# io_board.net
KiCad netlist of a schematic drawn in EAGLE
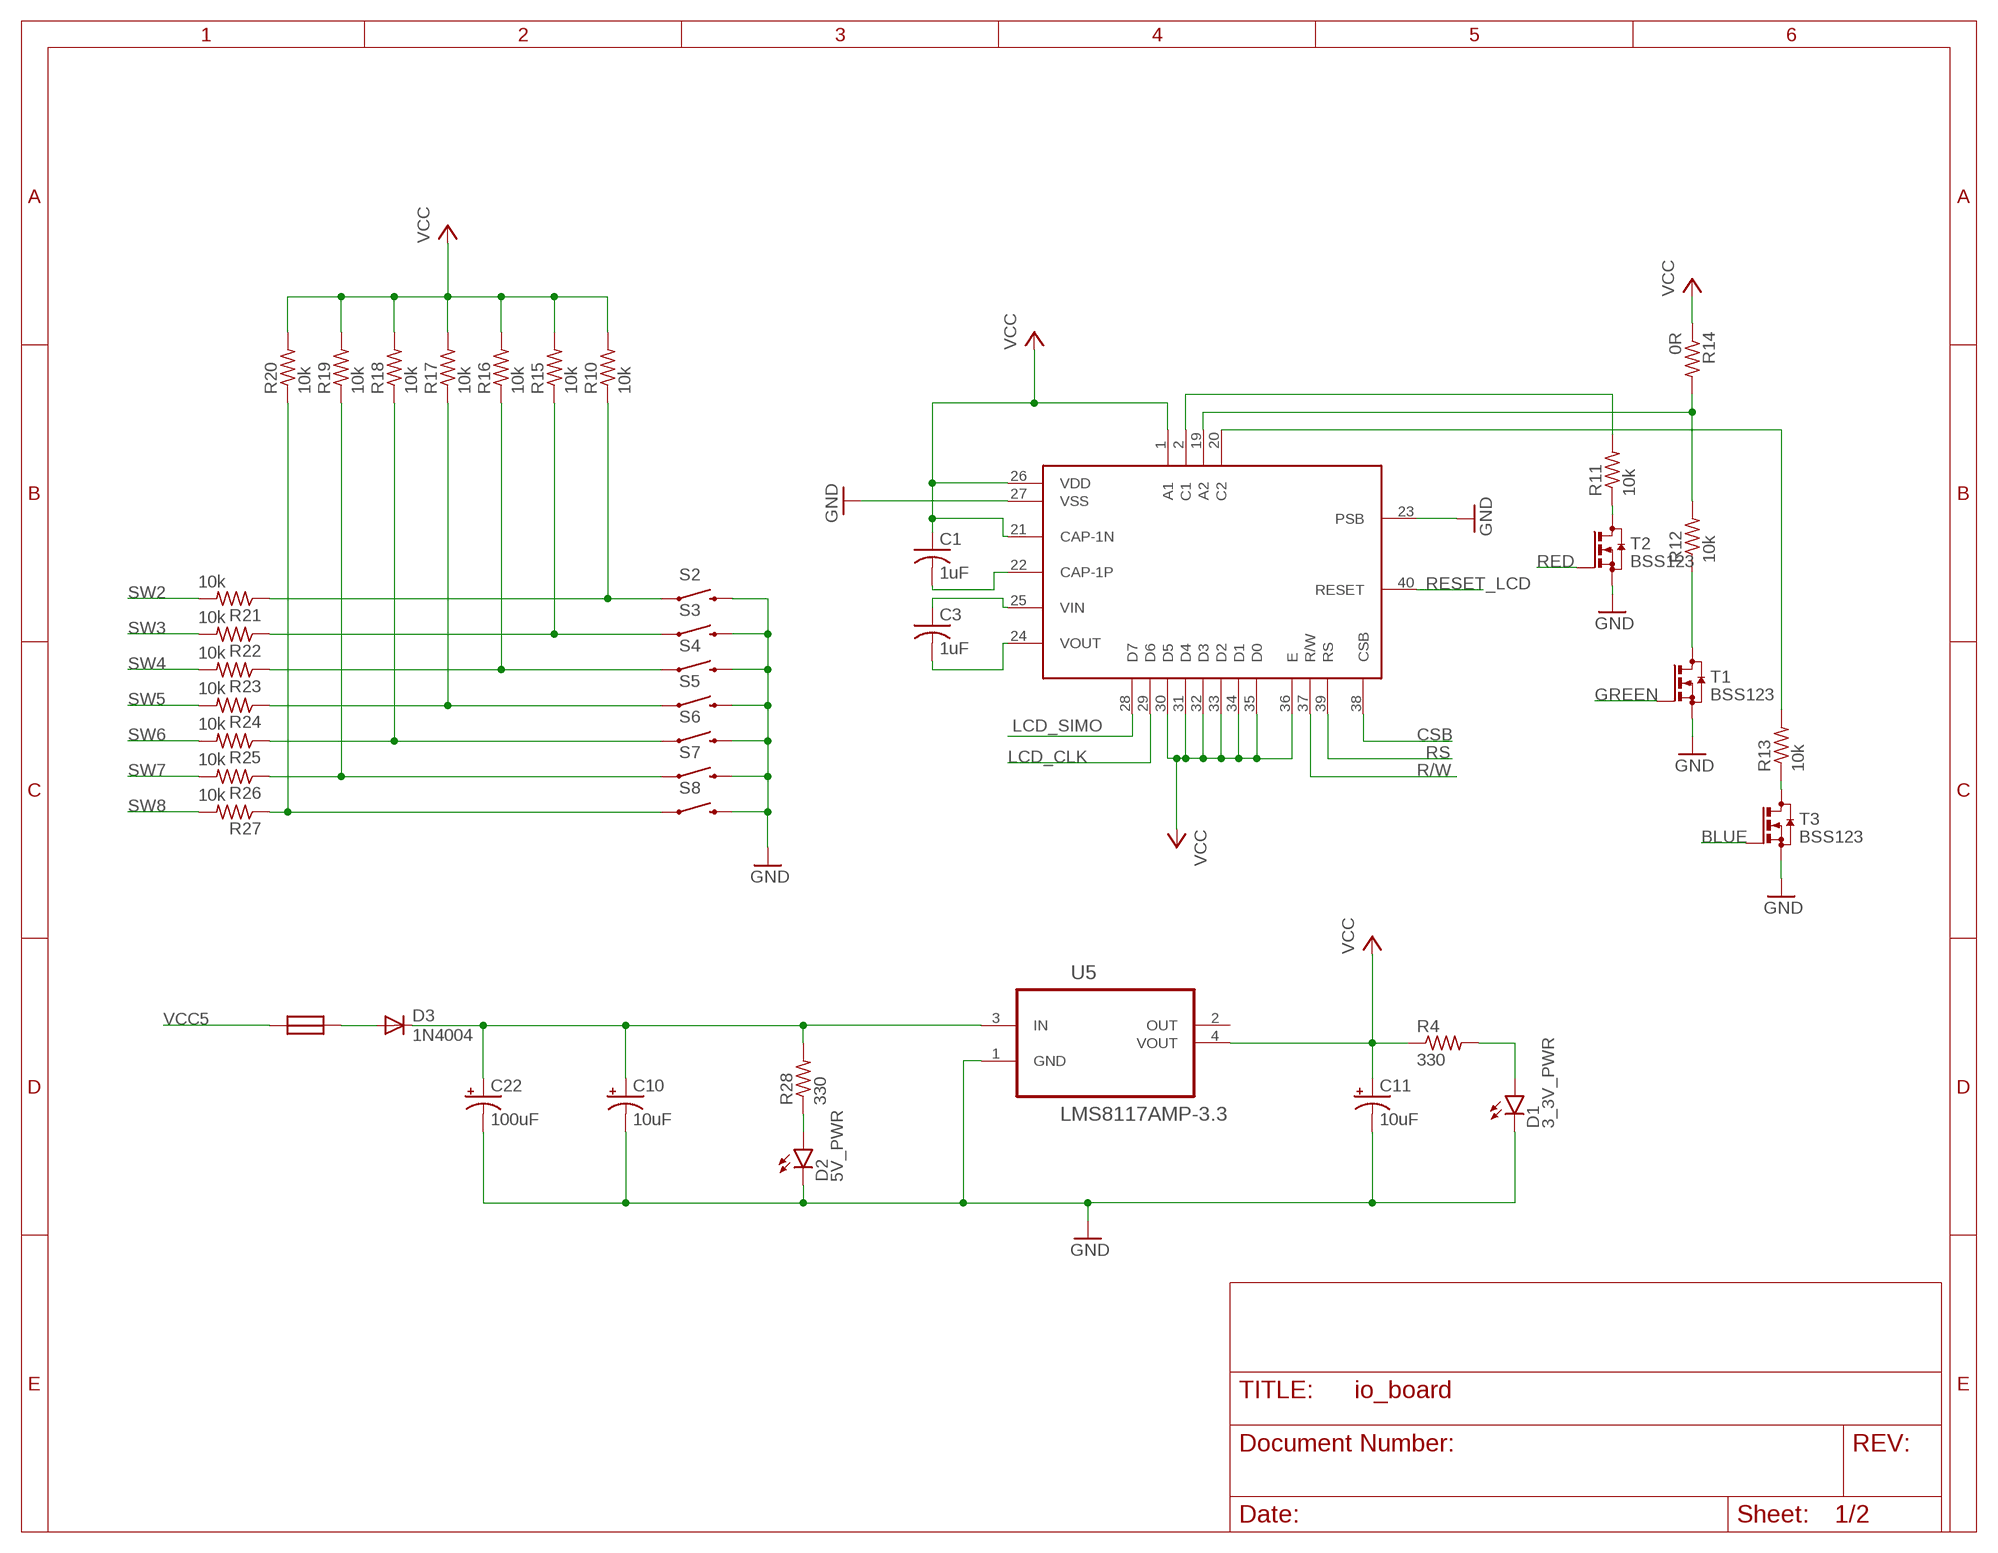
[diagram p0: schematic, sheet 1]
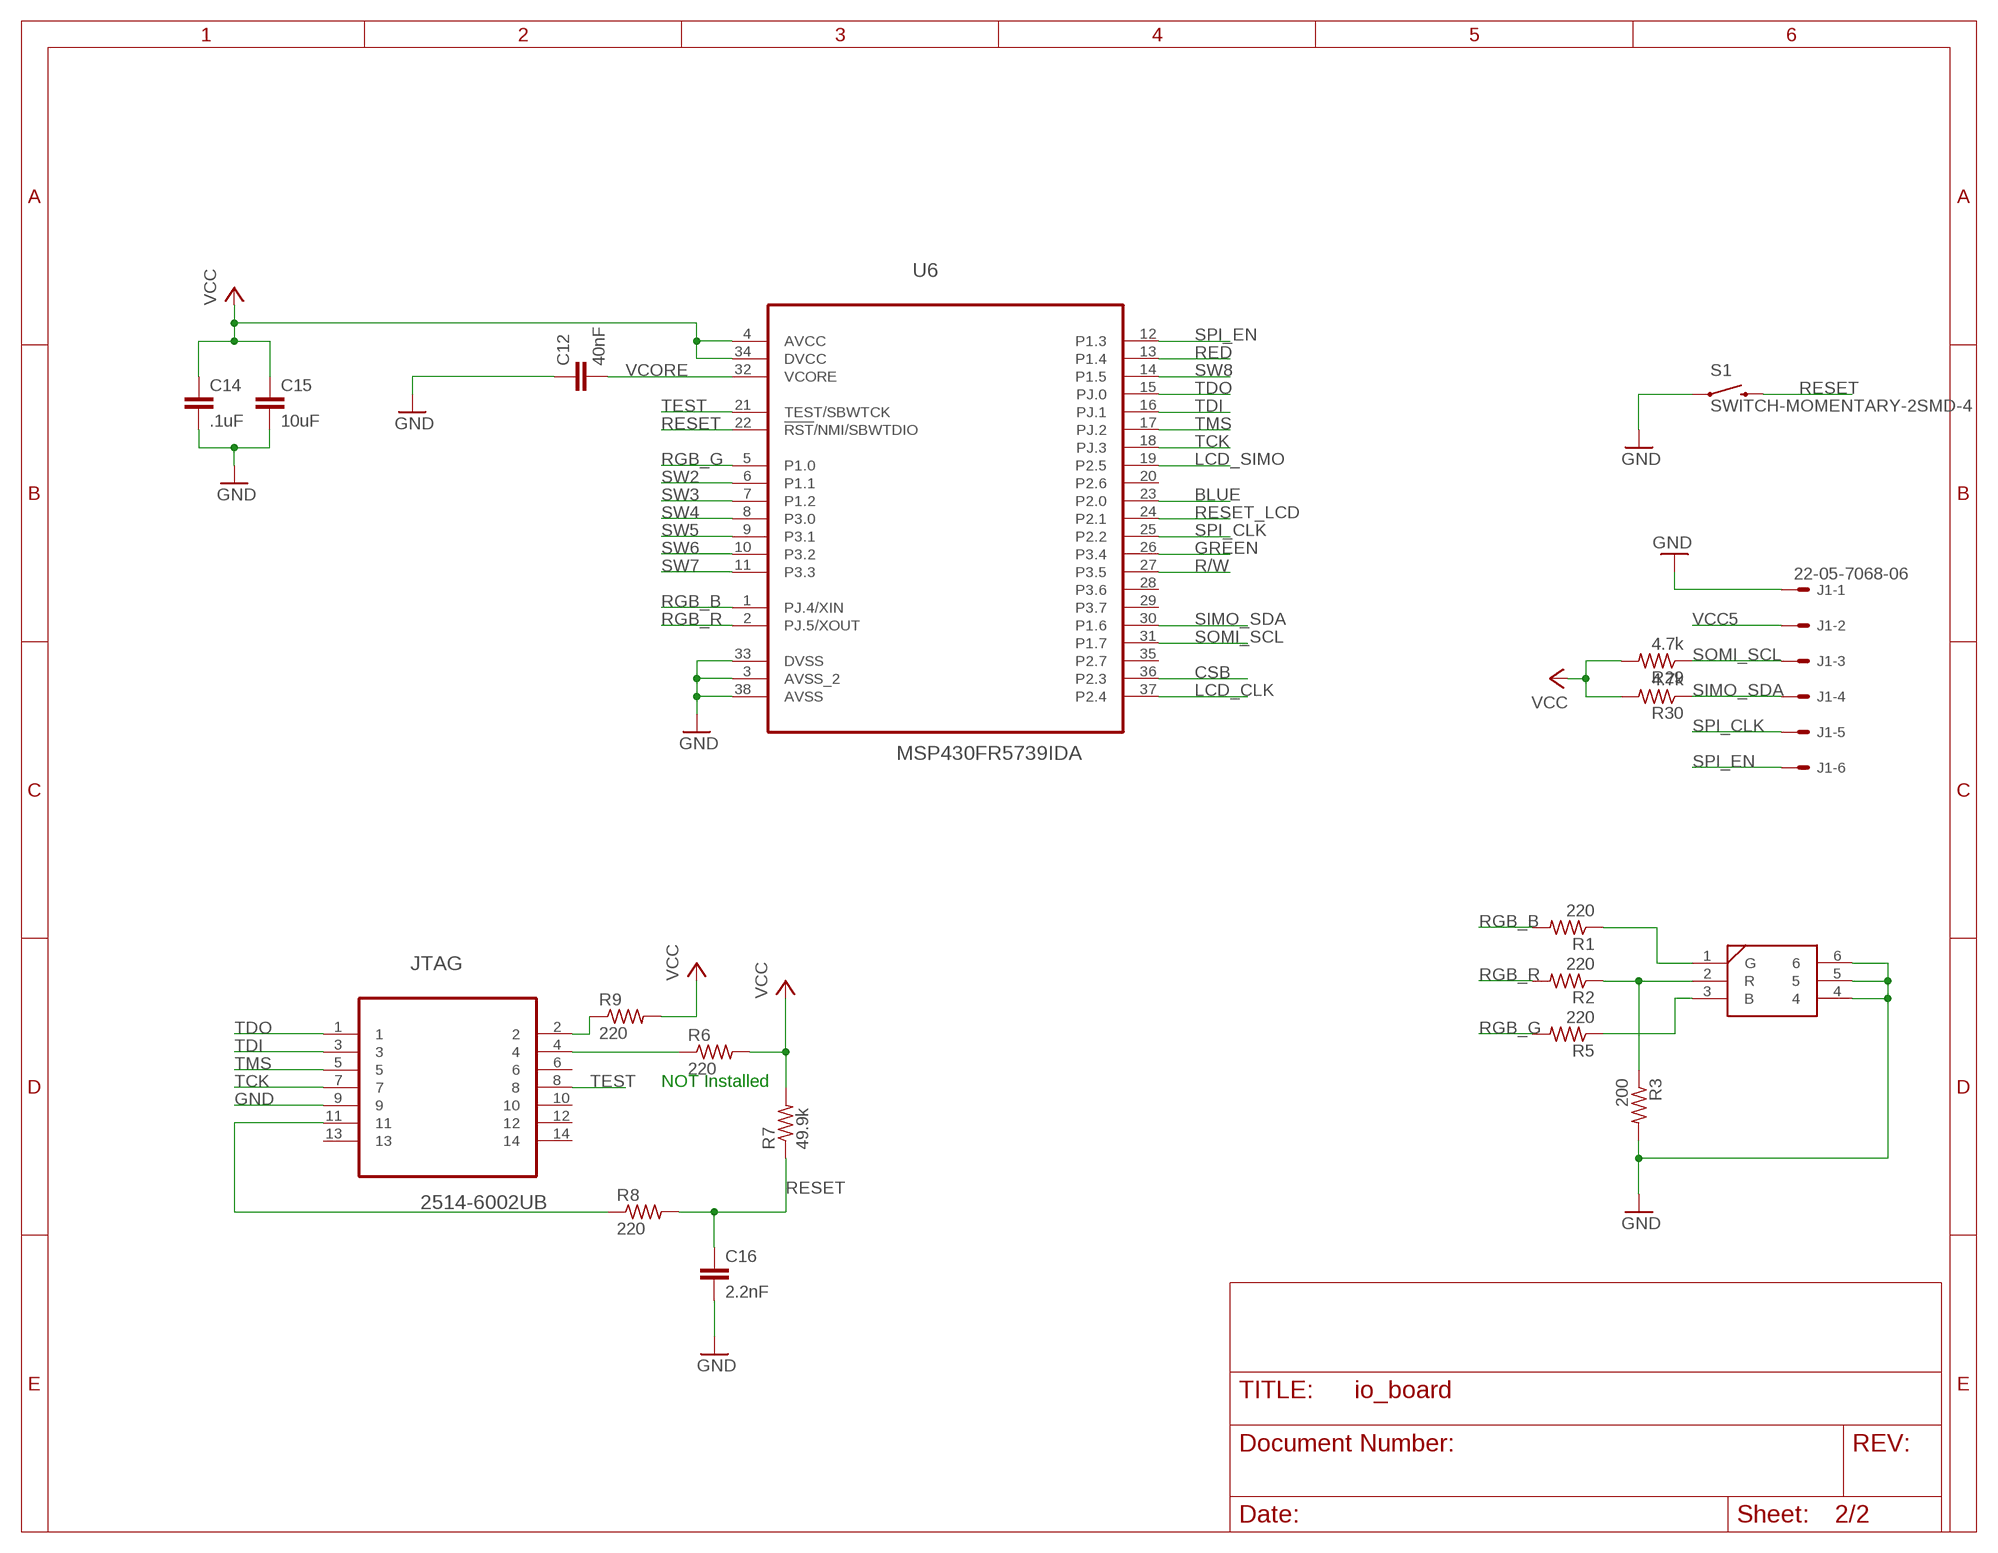
[diagram p1: schematic, sheet 2]

(export (version "E")
  (design (tool "Eeschema 10.0.6"))
  (components
    (comp (ref "C1")
      (value "1uF")
      (footprint "eagle-import:C1206K")
      (libsource (lib "eagle-import") (part "C-USC1206K"))
    )
    (comp (ref "C3")
      (value "1uF")
      (footprint "eagle-import:C1206K")
      (libsource (lib "eagle-import") (part "C-USC1206K"))
    )
    (comp (ref "C10")
      (value "10uF")
      (footprint "eagle-import:EIA3216")
      (libsource (lib "eagle-import") (part "10UF-16V-10%(TANT)"))
    )
    (comp (ref "C11")
      (value "10uF")
      (footprint "eagle-import:EIA3216")
      (libsource (lib "eagle-import") (part "10UF-16V-10%(TANT)"))
    )
    (comp (ref "C22")
      (value "100uF")
      (footprint "eagle-import:EIA7343")
      (libsource (lib "eagle-import") (part "100UF-10V-10%(TANT)"))
    )
    (comp (ref "D1")
      (value "3_3V_PWR")
      (footprint "eagle-import:FKIT-LED-1206")
      (libsource (lib "eagle-import") (part "LED-FKIT-1206"))
    )
    (comp (ref "D2")
      (value "5V_PWR")
      (footprint "eagle-import:FKIT-LED-1206")
      (libsource (lib "eagle-import") (part "LED-FKIT-1206"))
    )
    (comp (ref "D3")
      (value "1N4004")
      (footprint "eagle-import:DO41-10")
      (libsource (lib "eagle-import") (part "1N4004"))
    )
    (comp (ref "R4")
      (value "330")
      (footprint "eagle-import:R0805W")
      (libsource (lib "eagle-import") (part "R-US_R0805W"))
    )
    (comp (ref "R10")
      (value "10k")
      (footprint "eagle-import:R1206W")
      (libsource (lib "eagle-import") (part "R-US_R1206W"))
    )
    (comp (ref "R11")
      (value "10k")
      (footprint "eagle-import:R1206W")
      (libsource (lib "eagle-import") (part "R-US_R1206W"))
    )
    (comp (ref "R12")
      (value "10k")
      (footprint "eagle-import:R1206W")
      (libsource (lib "eagle-import") (part "R-US_R1206W"))
    )
    (comp (ref "R13")
      (value "10k")
      (footprint "eagle-import:R1206W")
      (libsource (lib "eagle-import") (part "R-US_R1206W"))
    )
    (comp (ref "R14")
      (value "0R")
      (footprint "eagle-import:R1206W")
      (libsource (lib "eagle-import") (part "R-US_R1206W"))
    )
    (comp (ref "R15")
      (value "10k")
      (footprint "eagle-import:R1206W")
      (libsource (lib "eagle-import") (part "R-US_R1206W"))
    )
    (comp (ref "R16")
      (value "10k")
      (footprint "eagle-import:R1206W")
      (libsource (lib "eagle-import") (part "R-US_R1206W"))
    )
    (comp (ref "R17")
      (value "10k")
      (footprint "eagle-import:R1206W")
      (libsource (lib "eagle-import") (part "R-US_R1206W"))
    )
    (comp (ref "R18")
      (value "10k")
      (footprint "eagle-import:R1206W")
      (libsource (lib "eagle-import") (part "R-US_R1206W"))
    )
    (comp (ref "R19")
      (value "10k")
      (footprint "eagle-import:R1206W")
      (libsource (lib "eagle-import") (part "R-US_R1206W"))
    )
    (comp (ref "R20")
      (value "10k")
      (footprint "eagle-import:R1206W")
      (libsource (lib "eagle-import") (part "R-US_R1206W"))
    )
    (comp (ref "R21")
      (value "10k")
      (footprint "eagle-import:R1206W")
      (libsource (lib "eagle-import") (part "R-US_R1206W"))
    )
    (comp (ref "R22")
      (value "10k")
      (footprint "eagle-import:R1206W")
      (libsource (lib "eagle-import") (part "R-US_R1206W"))
    )
    (comp (ref "R23")
      (value "10k")
      (footprint "eagle-import:R1206W")
      (libsource (lib "eagle-import") (part "R-US_R1206W"))
    )
    (comp (ref "R24")
      (value "10k")
      (footprint "eagle-import:R1206W")
      (libsource (lib "eagle-import") (part "R-US_R1206W"))
    )
    (comp (ref "R25")
      (value "10k")
      (footprint "eagle-import:R1206W")
      (libsource (lib "eagle-import") (part "R-US_R1206W"))
    )
    (comp (ref "R26")
      (value "10k")
      (footprint "eagle-import:R1206W")
      (libsource (lib "eagle-import") (part "R-US_R1206W"))
    )
    (comp (ref "R27")
      (value "10k")
      (footprint "eagle-import:R1206W")
      (libsource (lib "eagle-import") (part "R-US_R1206W"))
    )
    (comp (ref "R28")
      (value "330")
      (footprint "eagle-import:R0805W")
      (libsource (lib "eagle-import") (part "R-US_R0805W"))
    )
    (comp (ref "S2")
      (value "SWITCH-MOMENTARY-2SMD-4")
      (footprint "eagle-import:TACTILE_SWITCH_TALL")
      (libsource (lib "eagle-import") (part "SWITCH-MOMENTARY-2SMD-4"))
    )
    (comp (ref "S3")
      (value "SWITCH-MOMENTARY-2SMD-4")
      (footprint "eagle-import:TACTILE_SWITCH_TALL")
      (libsource (lib "eagle-import") (part "SWITCH-MOMENTARY-2SMD-4"))
    )
    (comp (ref "S4")
      (value "SWITCH-MOMENTARY-2SMD-4")
      (footprint "eagle-import:TACTILE_SWITCH_TALL")
      (libsource (lib "eagle-import") (part "SWITCH-MOMENTARY-2SMD-4"))
    )
    (comp (ref "S5")
      (value "SWITCH-MOMENTARY-2SMD-4")
      (footprint "eagle-import:TACTILE_SWITCH_TALL")
      (libsource (lib "eagle-import") (part "SWITCH-MOMENTARY-2SMD-4"))
    )
    (comp (ref "S6")
      (value "SWITCH-MOMENTARY-2SMD-4")
      (footprint "eagle-import:TACTILE_SWITCH_TALL")
      (libsource (lib "eagle-import") (part "SWITCH-MOMENTARY-2SMD-4"))
    )
    (comp (ref "S7")
      (value "SWITCH-MOMENTARY-2SMD-4")
      (footprint "eagle-import:TACTILE_SWITCH_TALL")
      (libsource (lib "eagle-import") (part "SWITCH-MOMENTARY-2SMD-4"))
    )
    (comp (ref "S8")
      (value "SWITCH-MOMENTARY-2SMD-4")
      (footprint "eagle-import:TACTILE_SWITCH_TALL")
      (libsource (lib "eagle-import") (part "SWITCH-MOMENTARY-2SMD-4"))
    )
    (comp (ref "T1")
      (value "BSS123")
      (footprint "eagle-import:SOT23")
      (libsource (lib "eagle-import") (part "BSS123"))
    )
    (comp (ref "T2")
      (value "BSS123")
      (footprint "eagle-import:SOT23")
      (libsource (lib "eagle-import") (part "BSS123"))
    )
    (comp (ref "T3")
      (value "BSS123")
      (footprint "eagle-import:SOT23")
      (libsource (lib "eagle-import") (part "BSS123"))
    )
    (comp (ref "U$2")
      (value "EA_DOGMXXX-A")
      (footprint "eagle-import:EADOGM")
      (libsource (lib "eagle-import") (part "EA_DOGMXXX-A"))
    )
    (comp (ref "U$3")
      (value "NANO_FUSE")
      (footprint "eagle-import:NANO_FUSE")
      (libsource (lib "eagle-import") (part "NANO_FUSE"))
    )
    (comp (ref "U5")
      (value "LMS8117AMP-3.3")
      (footprint "eagle-import:SOT230P696X180-4N")
      (libsource (lib "eagle-import") (part "LMS8117AMP-3.3"))
    )
    (comp (ref "C12")
      (value "40nF")
      (footprint "eagle-import:0805")
      (libsource (lib "eagle-import") (part "CAP0805"))
    )
    (comp (ref "C14")
      (value ".1uF")
      (footprint "eagle-import:0805")
      (libsource (lib "eagle-import") (part "CAP0805"))
    )
    (comp (ref "C15")
      (value "10uF")
      (footprint "eagle-import:0805")
      (libsource (lib "eagle-import") (part "CAP0805"))
    )
    (comp (ref "C16")
      (value "2.2nF")
      (footprint "eagle-import:0805")
      (libsource (lib "eagle-import") (part "CAP0805"))
    )
    (comp (ref "J1")
      (value "22-05-7068-06")
      (footprint "eagle-import:7395-06")
      (libsource (lib "eagle-import") (part "22-?-0605-7068"))
    )
    (comp (ref "JTAG")
      (value "2514-6002UB")
      (footprint "eagle-import:3M_2514-6002UB")
      (libsource (lib "eagle-import") (part "2514-6002UB"))
    )
    (comp (ref "R1")
      (value "220")
      (footprint "eagle-import:R0805W")
      (libsource (lib "eagle-import") (part "R-US_R0805W"))
    )
    (comp (ref "R2")
      (value "220")
      (footprint "eagle-import:R0805W")
      (libsource (lib "eagle-import") (part "R-US_R0805W"))
    )
    (comp (ref "R3")
      (value "200")
      (footprint "eagle-import:R0805W")
      (libsource (lib "eagle-import") (part "R-US_R0805W"))
    )
    (comp (ref "R5")
      (value "220")
      (footprint "eagle-import:R0805W")
      (libsource (lib "eagle-import") (part "R-US_R0805W"))
    )
    (comp (ref "R6")
      (value "220")
      (footprint "eagle-import:R0805W")
      (libsource (lib "eagle-import") (part "R-US_R0805W"))
    )
    (comp (ref "R7")
      (value "49.9k")
      (footprint "eagle-import:R0805W")
      (libsource (lib "eagle-import") (part "R-US_R0805W"))
    )
    (comp (ref "R8")
      (value "220")
      (footprint "eagle-import:R0805W")
      (libsource (lib "eagle-import") (part "R-US_R0805W"))
    )
    (comp (ref "R9")
      (value "220")
      (footprint "eagle-import:R0805W")
      (libsource (lib "eagle-import") (part "R-US_R0805W"))
    )
    (comp (ref "R29")
      (value "4.7k")
      (footprint "eagle-import:R0805W")
      (libsource (lib "eagle-import") (part "R-US_R0805W"))
    )
    (comp (ref "R30")
      (value "4.7k")
      (footprint "eagle-import:R0805W")
      (libsource (lib "eagle-import") (part "R-US_R0805W"))
    )
    (comp (ref "S1")
      (value "SWITCH-MOMENTARY-2SMD-4")
      (footprint "eagle-import:TACTILE_SWITCH_TALL")
      (libsource (lib "eagle-import") (part "SWITCH-MOMENTARY-2SMD-4"))
    )
    (comp (ref "U$7")
      (value "RGB")
      (footprint "eagle-import:RGB_SMD")
      (libsource (lib "eagle-import") (part "RGB"))
    )
    (comp (ref "U6")
      (value "MSP430FR5739IDA")
      (footprint "eagle-import:SOP65P810X120-38N")
      (fields (field (name "MPN") "MSP430FR5739IDA "))
      (libsource (lib "eagle-import") (part "MSP430FR5739IDA"))
    )
  )
  (nets
    (net (code "1") (name "BLUE") (class "Default")
      (node (ref "T3") (pin "1") (pinfunction "G_1") (pintype "passive"))
      (node (ref "U6") (pin "23") (pinfunction "P2.0_23") (pintype "bidirectional"))
    )
    (net (code "2") (name "CSB") (class "Default")
      (node (ref "U$2") (pin "38") (pinfunction "CSB_38") (pintype "bidirectional"))
      (node (ref "U6") (pin "36") (pinfunction "P2.3_36") (pintype "bidirectional"))
    )
    (net (code "3") (name "GND") (class "Default")
      (node (ref "C10") (pin "C") (pinfunction "-_C") (pintype "passive"))
      (node (ref "C11") (pin "C") (pinfunction "-_C") (pintype "passive"))
      (node (ref "C12") (pin "1") (pinfunction "1_1") (pintype "passive"))
      (node (ref "C14") (pin "2") (pinfunction "2_2") (pintype "passive"))
      (node (ref "C15") (pin "2") (pinfunction "2_2") (pintype "passive"))
      (node (ref "C16") (pin "2") (pinfunction "2_2") (pintype "passive"))
      (node (ref "C22") (pin "C") (pinfunction "-_C") (pintype "passive"))
      (node (ref "D1") (pin "C") (pinfunction "C_C") (pintype "passive"))
      (node (ref "D2") (pin "C") (pinfunction "C_C") (pintype "passive"))
      (node (ref "J1") (pin "1") (pinfunction "S_1") (pintype "passive"))
      (node (ref "JTAG") (pin "9") (pinfunction "9_9") (pintype "passive"))
      (node (ref "R3") (pin "2") (pinfunction "2_2") (pintype "passive"))
      (node (ref "S1") (pin "A2") (pinfunction "1_A2") (pintype "passive"))
      (node (ref "S2") (pin "B2") (pinfunction "2_B2") (pintype "passive"))
      (node (ref "S3") (pin "B2") (pinfunction "2_B2") (pintype "passive"))
      (node (ref "S4") (pin "B2") (pinfunction "2_B2") (pintype "passive"))
      (node (ref "S5") (pin "B2") (pinfunction "2_B2") (pintype "passive"))
      (node (ref "S6") (pin "B2") (pinfunction "2_B2") (pintype "passive"))
      (node (ref "S7") (pin "B2") (pinfunction "2_B2") (pintype "passive"))
      (node (ref "S8") (pin "B2") (pinfunction "2_B2") (pintype "passive"))
      (node (ref "T1") (pin "2") (pinfunction "S_2") (pintype "passive"))
      (node (ref "T2") (pin "2") (pinfunction "S_2") (pintype "passive"))
      (node (ref "T3") (pin "2") (pinfunction "S_2") (pintype "passive"))
      (node (ref "U$2") (pin "23") (pinfunction "PSB_23") (pintype "bidirectional"))
      (node (ref "U$2") (pin "27") (pinfunction "VSS_27") (pintype "bidirectional"))
      (node (ref "U$7") (pin "4") (pinfunction "4_4") (pintype "bidirectional"))
      (node (ref "U$7") (pin "5") (pinfunction "5_5") (pintype "bidirectional"))
      (node (ref "U$7") (pin "6") (pinfunction "6_6") (pintype "bidirectional"))
      (node (ref "U5") (pin "1") (pinfunction "GND_1") (pintype "passive"))
      (node (ref "U6") (pin "3") (pinfunction "AVSS_2_3") (pintype "passive"))
      (node (ref "U6") (pin "33") (pinfunction "DVSS_33") (pintype "passive"))
      (node (ref "U6") (pin "38") (pinfunction "AVSS_38") (pintype "passive"))
    )
    (net (code "4") (name "GREEN") (class "Default")
      (node (ref "T1") (pin "1") (pinfunction "G_1") (pintype "passive"))
      (node (ref "U6") (pin "26") (pinfunction "P3.4_26") (pintype "bidirectional"))
    )
    (net (code "5") (name "LCD_CLK") (class "Default")
      (node (ref "U$2") (pin "29") (pinfunction "D6_29") (pintype "bidirectional"))
      (node (ref "U6") (pin "37") (pinfunction "P2.4_37") (pintype "bidirectional"))
    )
    (net (code "6") (name "LCD_SIMO") (class "Default")
      (node (ref "U$2") (pin "28") (pinfunction "D7_28") (pintype "bidirectional"))
      (node (ref "U6") (pin "19") (pinfunction "P2.5_19") (pintype "bidirectional"))
    )
    (net (code "7") (name "Net-(C10-+)") (class "Default")
      (node (ref "C10") (pin "A") (pinfunction "+_A") (pintype "passive"))
      (node (ref "C22") (pin "A") (pinfunction "+_A") (pintype "passive"))
      (node (ref "D3") (pin "C") (pinfunction "C_C") (pintype "passive"))
      (node (ref "R28") (pin "2") (pinfunction "2_2") (pintype "passive"))
      (node (ref "U5") (pin "3") (pinfunction "IN_3") (pintype "power_in"))
    )
    (net (code "8") (name "Net-(D1-PadA)") (class "Default")
      (node (ref "D1") (pin "A") (pinfunction "A_A") (pintype "passive"))
      (node (ref "R4") (pin "2") (pinfunction "2_2") (pintype "passive"))
    )
    (net (code "9") (name "Net-(D2-PadA)") (class "Default")
      (node (ref "D2") (pin "A") (pinfunction "A_A") (pintype "passive"))
      (node (ref "R28") (pin "1") (pinfunction "1_1") (pintype "passive"))
    )
    (net (code "10") (name "Net-(D3-PadA)") (class "Default")
      (node (ref "D3") (pin "A") (pinfunction "A_A") (pintype "passive"))
      (node (ref "U$3") (pin "2") (pinfunction "2_2") (pintype "bidirectional"))
    )
    (net (code "11") (name "Net-(JTAG-Pad2)") (class "Default")
      (node (ref "JTAG") (pin "2") (pinfunction "2_2") (pintype "passive"))
      (node (ref "R9") (pin "1") (pinfunction "1_1") (pintype "passive"))
    )
    (net (code "12") (name "Net-(JTAG-Pad4)") (class "Default")
      (node (ref "JTAG") (pin "4") (pinfunction "4_4") (pintype "passive"))
      (node (ref "R6") (pin "1") (pinfunction "1_1") (pintype "passive"))
    )
    (net (code "13") (name "Net-(JTAG-Pad11)") (class "Default")
      (node (ref "JTAG") (pin "11") (pinfunction "11_11") (pintype "passive"))
      (node (ref "R8") (pin "1") (pinfunction "1_1") (pintype "passive"))
    )
    (net (code "14") (name "Net-(S2-1)") (class "Default")
      (node (ref "R10") (pin "1") (pinfunction "1_1") (pintype "passive"))
      (node (ref "R21") (pin "1") (pinfunction "1_1") (pintype "passive"))
      (node (ref "S2") (pin "A2") (pinfunction "1_A2") (pintype "passive"))
    )
    (net (code "15") (name "Net-(S3-1)") (class "Default")
      (node (ref "R15") (pin "1") (pinfunction "1_1") (pintype "passive"))
      (node (ref "R22") (pin "1") (pinfunction "1_1") (pintype "passive"))
      (node (ref "S3") (pin "A2") (pinfunction "1_A2") (pintype "passive"))
    )
    (net (code "16") (name "Net-(S4-1)") (class "Default")
      (node (ref "R16") (pin "1") (pinfunction "1_1") (pintype "passive"))
      (node (ref "R23") (pin "1") (pinfunction "1_1") (pintype "passive"))
      (node (ref "S4") (pin "A2") (pinfunction "1_A2") (pintype "passive"))
    )
    (net (code "17") (name "Net-(S5-1)") (class "Default")
      (node (ref "R17") (pin "1") (pinfunction "1_1") (pintype "passive"))
      (node (ref "R24") (pin "1") (pinfunction "1_1") (pintype "passive"))
      (node (ref "S5") (pin "A2") (pinfunction "1_A2") (pintype "passive"))
    )
    (net (code "18") (name "Net-(S6-1)") (class "Default")
      (node (ref "R18") (pin "1") (pinfunction "1_1") (pintype "passive"))
      (node (ref "R25") (pin "1") (pinfunction "1_1") (pintype "passive"))
      (node (ref "S6") (pin "A2") (pinfunction "1_A2") (pintype "passive"))
    )
    (net (code "19") (name "Net-(S7-1)") (class "Default")
      (node (ref "R19") (pin "1") (pinfunction "1_1") (pintype "passive"))
      (node (ref "R26") (pin "1") (pinfunction "1_1") (pintype "passive"))
      (node (ref "S7") (pin "A2") (pinfunction "1_A2") (pintype "passive"))
    )
    (net (code "20") (name "Net-(S8-1)") (class "Default")
      (node (ref "R20") (pin "1") (pinfunction "1_1") (pintype "passive"))
      (node (ref "R27") (pin "1") (pinfunction "1_1") (pintype "passive"))
      (node (ref "S8") (pin "A2") (pinfunction "1_A2") (pintype "passive"))
    )
    (net (code "21") (name "Net-(T1-D)") (class "Default")
      (node (ref "R12") (pin "1") (pinfunction "1_1") (pintype "passive"))
      (node (ref "T1") (pin "3") (pinfunction "D_3") (pintype "passive"))
    )
    (net (code "22") (name "Net-(T2-D)") (class "Default")
      (node (ref "R11") (pin "1") (pinfunction "1_1") (pintype "passive"))
      (node (ref "T2") (pin "3") (pinfunction "D_3") (pintype "passive"))
    )
    (net (code "23") (name "Net-(T3-D)") (class "Default")
      (node (ref "R13") (pin "1") (pinfunction "1_1") (pintype "passive"))
      (node (ref "T3") (pin "3") (pinfunction "D_3") (pintype "passive"))
    )
    (net (code "24") (name "Net-(U$2-A2)") (class "Default")
      (node (ref "R12") (pin "2") (pinfunction "2_2") (pintype "passive"))
      (node (ref "R14") (pin "2") (pinfunction "2_2") (pintype "passive"))
      (node (ref "U$2") (pin "19") (pinfunction "A2_19") (pintype "bidirectional"))
    )
    (net (code "25") (name "Net-(U$2-C1)") (class "Default")
      (node (ref "R11") (pin "2") (pinfunction "2_2") (pintype "passive"))
      (node (ref "U$2") (pin "2") (pinfunction "C1_2") (pintype "bidirectional"))
    )
    (net (code "26") (name "Net-(U$2-C2)") (class "Default")
      (node (ref "R13") (pin "2") (pinfunction "2_2") (pintype "passive"))
      (node (ref "U$2") (pin "20") (pinfunction "C2_20") (pintype "bidirectional"))
    )
    (net (code "27") (name "Net-(U$2-CAP-1P)") (class "Default")
      (node (ref "C1") (pin "2") (pinfunction "2_2") (pintype "passive"))
      (node (ref "U$2") (pin "22") (pinfunction "CAP-1P_22") (pintype "bidirectional"))
    )
    (net (code "28") (name "Net-(U$2-VIN)") (class "Default")
      (node (ref "C3") (pin "1") (pinfunction "1_1") (pintype "passive"))
      (node (ref "U$2") (pin "25") (pinfunction "VIN_25") (pintype "bidirectional"))
    )
    (net (code "29") (name "Net-(U$2-VOUT)") (class "Default")
      (node (ref "C3") (pin "2") (pinfunction "2_2") (pintype "passive"))
      (node (ref "U$2") (pin "24") (pinfunction "VOUT_24") (pintype "bidirectional"))
    )
    (net (code "30") (name "Net-(U$7-B)") (class "Default")
      (node (ref "R5") (pin "1") (pinfunction "1_1") (pintype "passive"))
      (node (ref "U$7") (pin "3") (pinfunction "B_3") (pintype "bidirectional"))
    )
    (net (code "31") (name "Net-(U$7-G)") (class "Default")
      (node (ref "R1") (pin "1") (pinfunction "1_1") (pintype "passive"))
      (node (ref "U$7") (pin "1") (pinfunction "G_1") (pintype "bidirectional"))
    )
    (net (code "32") (name "Net-(U$7-R)") (class "Default")
      (node (ref "R2") (pin "1") (pinfunction "1_1") (pintype "passive"))
      (node (ref "R3") (pin "1") (pinfunction "1_1") (pintype "passive"))
      (node (ref "U$7") (pin "2") (pinfunction "R_2") (pintype "bidirectional"))
    )
    (net (code "33") (name "RED") (class "Default")
      (node (ref "T2") (pin "1") (pinfunction "G_1") (pintype "passive"))
      (node (ref "U6") (pin "13") (pinfunction "P1.4_13") (pintype "bidirectional"))
    )
    (net (code "34") (name "RESET") (class "Default")
      (node (ref "C16") (pin "1") (pinfunction "1_1") (pintype "passive"))
      (node (ref "R7") (pin "1") (pinfunction "1_1") (pintype "passive"))
      (node (ref "R8") (pin "2") (pinfunction "2_2") (pintype "passive"))
      (node (ref "S1") (pin "B2") (pinfunction "2_B2") (pintype "passive"))
      (node (ref "U6") (pin "22") (pinfunction "~{RST}/NMI/SBWTDIO_22") (pintype "input"))
    )
    (net (code "35") (name "RESET_LCD") (class "Default")
      (node (ref "U$2") (pin "40") (pinfunction "RESET_40") (pintype "bidirectional"))
      (node (ref "U6") (pin "24") (pinfunction "P2.1_24") (pintype "bidirectional"))
    )
    (net (code "36") (name "RGB_B") (class "Default")
      (node (ref "R1") (pin "2") (pinfunction "2_2") (pintype "passive"))
      (node (ref "U6") (pin "1") (pinfunction "PJ.4/XIN_1") (pintype "bidirectional"))
    )
    (net (code "37") (name "RGB_G") (class "Default")
      (node (ref "R5") (pin "2") (pinfunction "2_2") (pintype "passive"))
      (node (ref "U6") (pin "5") (pinfunction "P1.0_5") (pintype "bidirectional"))
    )
    (net (code "38") (name "RGB_R") (class "Default")
      (node (ref "R2") (pin "2") (pinfunction "2_2") (pintype "passive"))
      (node (ref "U6") (pin "2") (pinfunction "PJ.5/XOUT_2") (pintype "bidirectional"))
    )
    (net (code "39") (name "RS") (class "Default")
      (node (ref "U$2") (pin "39") (pinfunction "RS_39") (pintype "bidirectional"))
    )
    (net (code "40") (name "R{slash}W") (class "Default")
      (node (ref "U$2") (pin "37") (pinfunction "R/W_37") (pintype "bidirectional"))
      (node (ref "U6") (pin "27") (pinfunction "P3.5_27") (pintype "bidirectional"))
    )
    (net (code "41") (name "SIMO_SDA") (class "Default")
      (node (ref "J1") (pin "4") (pinfunction "S_4") (pintype "passive"))
      (node (ref "R30") (pin "1") (pinfunction "1_1") (pintype "passive"))
      (node (ref "U6") (pin "30") (pinfunction "P1.6_30") (pintype "bidirectional"))
    )
    (net (code "42") (name "SOMI_SCL") (class "Default")
      (node (ref "J1") (pin "3") (pinfunction "S_3") (pintype "passive"))
      (node (ref "R29") (pin "1") (pinfunction "1_1") (pintype "passive"))
      (node (ref "U6") (pin "31") (pinfunction "P1.7_31") (pintype "bidirectional"))
    )
    (net (code "43") (name "SPI_CLK") (class "Default")
      (node (ref "J1") (pin "5") (pinfunction "S_5") (pintype "passive"))
      (node (ref "U6") (pin "25") (pinfunction "P2.2_25") (pintype "bidirectional"))
    )
    (net (code "44") (name "SPI_EN") (class "Default")
      (node (ref "J1") (pin "6") (pinfunction "S_6") (pintype "passive"))
      (node (ref "U6") (pin "12") (pinfunction "P1.3_12") (pintype "bidirectional"))
    )
    (net (code "45") (name "SW2") (class "Default")
      (node (ref "R21") (pin "2") (pinfunction "2_2") (pintype "passive"))
      (node (ref "U6") (pin "6") (pinfunction "P1.1_6") (pintype "bidirectional"))
    )
    (net (code "46") (name "SW3") (class "Default")
      (node (ref "R22") (pin "2") (pinfunction "2_2") (pintype "passive"))
      (node (ref "U6") (pin "7") (pinfunction "P1.2_7") (pintype "bidirectional"))
    )
    (net (code "47") (name "SW4") (class "Default")
      (node (ref "R23") (pin "2") (pinfunction "2_2") (pintype "passive"))
      (node (ref "U6") (pin "8") (pinfunction "P3.0_8") (pintype "bidirectional"))
    )
    (net (code "48") (name "SW5") (class "Default")
      (node (ref "R24") (pin "2") (pinfunction "2_2") (pintype "passive"))
      (node (ref "U6") (pin "9") (pinfunction "P3.1_9") (pintype "bidirectional"))
    )
    (net (code "49") (name "SW6") (class "Default")
      (node (ref "R25") (pin "2") (pinfunction "2_2") (pintype "passive"))
      (node (ref "U6") (pin "10") (pinfunction "P3.2_10") (pintype "bidirectional"))
    )
    (net (code "50") (name "SW7") (class "Default")
      (node (ref "R26") (pin "2") (pinfunction "2_2") (pintype "passive"))
      (node (ref "U6") (pin "11") (pinfunction "P3.3_11") (pintype "bidirectional"))
    )
    (net (code "51") (name "SW8") (class "Default")
      (node (ref "R27") (pin "2") (pinfunction "2_2") (pintype "passive"))
      (node (ref "U6") (pin "14") (pinfunction "P1.5_14") (pintype "bidirectional"))
    )
    (net (code "52") (name "TCK") (class "Default")
      (node (ref "JTAG") (pin "7") (pinfunction "7_7") (pintype "passive"))
      (node (ref "U6") (pin "18") (pinfunction "PJ.3_18") (pintype "bidirectional"))
    )
    (net (code "53") (name "TDI") (class "Default")
      (node (ref "JTAG") (pin "3") (pinfunction "3_3") (pintype "passive"))
      (node (ref "U6") (pin "16") (pinfunction "PJ.1_16") (pintype "bidirectional"))
    )
    (net (code "54") (name "TDO") (class "Default")
      (node (ref "JTAG") (pin "1") (pinfunction "1_1") (pintype "passive"))
      (node (ref "U6") (pin "15") (pinfunction "PJ.0_15") (pintype "bidirectional"))
    )
    (net (code "55") (name "TEST") (class "Default")
      (node (ref "JTAG") (pin "8") (pinfunction "8_8") (pintype "passive"))
      (node (ref "U6") (pin "21") (pinfunction "TEST/SBWTCK_21") (pintype "input"))
    )
    (net (code "56") (name "TMS") (class "Default")
      (node (ref "JTAG") (pin "5") (pinfunction "5_5") (pintype "passive"))
      (node (ref "U6") (pin "17") (pinfunction "PJ.2_17") (pintype "bidirectional"))
    )
    (net (code "57") (name "VCC") (class "Default")
      (node (ref "C1") (pin "1") (pinfunction "1_1") (pintype "passive"))
      (node (ref "C11") (pin "A") (pinfunction "+_A") (pintype "passive"))
      (node (ref "C14") (pin "1") (pinfunction "1_1") (pintype "passive"))
      (node (ref "C15") (pin "1") (pinfunction "1_1") (pintype "passive"))
      (node (ref "R10") (pin "2") (pinfunction "2_2") (pintype "passive"))
      (node (ref "R14") (pin "1") (pinfunction "1_1") (pintype "passive"))
      (node (ref "R15") (pin "2") (pinfunction "2_2") (pintype "passive"))
      (node (ref "R16") (pin "2") (pinfunction "2_2") (pintype "passive"))
      (node (ref "R17") (pin "2") (pinfunction "2_2") (pintype "passive"))
      (node (ref "R18") (pin "2") (pinfunction "2_2") (pintype "passive"))
      (node (ref "R19") (pin "2") (pinfunction "2_2") (pintype "passive"))
      (node (ref "R20") (pin "2") (pinfunction "2_2") (pintype "passive"))
      (node (ref "R29") (pin "2") (pinfunction "2_2") (pintype "passive"))
      (node (ref "R30") (pin "2") (pinfunction "2_2") (pintype "passive"))
      (node (ref "R4") (pin "1") (pinfunction "1_1") (pintype "passive"))
      (node (ref "R6") (pin "2") (pinfunction "2_2") (pintype "passive"))
      (node (ref "R7") (pin "2") (pinfunction "2_2") (pintype "passive"))
      (node (ref "R9") (pin "2") (pinfunction "2_2") (pintype "passive"))
      (node (ref "U$2") (pin "1") (pinfunction "A1_1") (pintype "bidirectional"))
      (node (ref "U$2") (pin "21") (pinfunction "CAP-1N_21") (pintype "bidirectional"))
      (node (ref "U$2") (pin "26") (pinfunction "VDD_26") (pintype "bidirectional"))
      (node (ref "U$2") (pin "30") (pinfunction "D5_30") (pintype "bidirectional"))
      (node (ref "U$2") (pin "31") (pinfunction "D4_31") (pintype "bidirectional"))
      (node (ref "U$2") (pin "32") (pinfunction "D3_32") (pintype "bidirectional"))
      (node (ref "U$2") (pin "33") (pinfunction "D2_33") (pintype "bidirectional"))
      (node (ref "U$2") (pin "34") (pinfunction "D1_34") (pintype "bidirectional"))
      (node (ref "U$2") (pin "35") (pinfunction "D0_35") (pintype "bidirectional"))
      (node (ref "U$2") (pin "36") (pinfunction "E_36") (pintype "bidirectional"))
      (node (ref "U5") (pin "4") (pinfunction "VOUT_4") (pintype "power_in"))
      (node (ref "U6") (pin "34") (pinfunction "DVCC_34") (pintype "power_in"))
      (node (ref "U6") (pin "4") (pinfunction "AVCC_4") (pintype "power_in"))
    )
    (net (code "58") (name "VCC5") (class "Default")
      (node (ref "J1") (pin "2") (pinfunction "S_2") (pintype "passive"))
      (node (ref "U$3") (pin "1") (pinfunction "1_1") (pintype "bidirectional"))
    )
    (net (code "59") (name "VCORE") (class "Default")
      (node (ref "C12") (pin "2") (pinfunction "2_2") (pintype "passive"))
      (node (ref "U6") (pin "32") (pinfunction "VCORE_32") (pintype "power_in"))
    )
    (net (code "60") (name "unconnected-(JTAG-Pad6)") (class "Default")
      (node (ref "JTAG") (pin "6") (pinfunction "6_6") (pintype "passive"))
    )
    (net (code "61") (name "unconnected-(JTAG-Pad10)") (class "Default")
      (node (ref "JTAG") (pin "10") (pinfunction "10_10") (pintype "passive"))
    )
    (net (code "62") (name "unconnected-(JTAG-Pad12)") (class "Default")
      (node (ref "JTAG") (pin "12") (pinfunction "12_12") (pintype "passive"))
    )
    (net (code "63") (name "unconnected-(JTAG-Pad13)") (class "Default")
      (node (ref "JTAG") (pin "13") (pinfunction "13_13") (pintype "passive"))
    )
    (net (code "64") (name "unconnected-(JTAG-Pad14)") (class "Default")
      (node (ref "JTAG") (pin "14") (pinfunction "14_14") (pintype "passive"))
    )
    (net (code "65") (name "unconnected-(U5-OUT-Pad2)") (class "Default")
      (node (ref "U5") (pin "2") (pinfunction "OUT_2") (pintype "output"))
    )
    (net (code "66") (name "unconnected-(U6-P2.6-Pad20)") (class "Default")
      (node (ref "U6") (pin "20") (pinfunction "P2.6_20") (pintype "bidirectional"))
    )
    (net (code "67") (name "unconnected-(U6-P2.7-Pad35)") (class "Default")
      (node (ref "U6") (pin "35") (pinfunction "P2.7_35") (pintype "bidirectional"))
    )
    (net (code "68") (name "unconnected-(U6-P3.6-Pad28)") (class "Default")
      (node (ref "U6") (pin "28") (pinfunction "P3.6_28") (pintype "bidirectional"))
    )
    (net (code "69") (name "unconnected-(U6-P3.7-Pad29)") (class "Default")
      (node (ref "U6") (pin "29") (pinfunction "P3.7_29") (pintype "bidirectional"))
    )
  )
)
